# SCH_M5_Stick_DCC_Interface_2022-09-24.net
KiCad netlist of a schematic drawn in EasyEDA
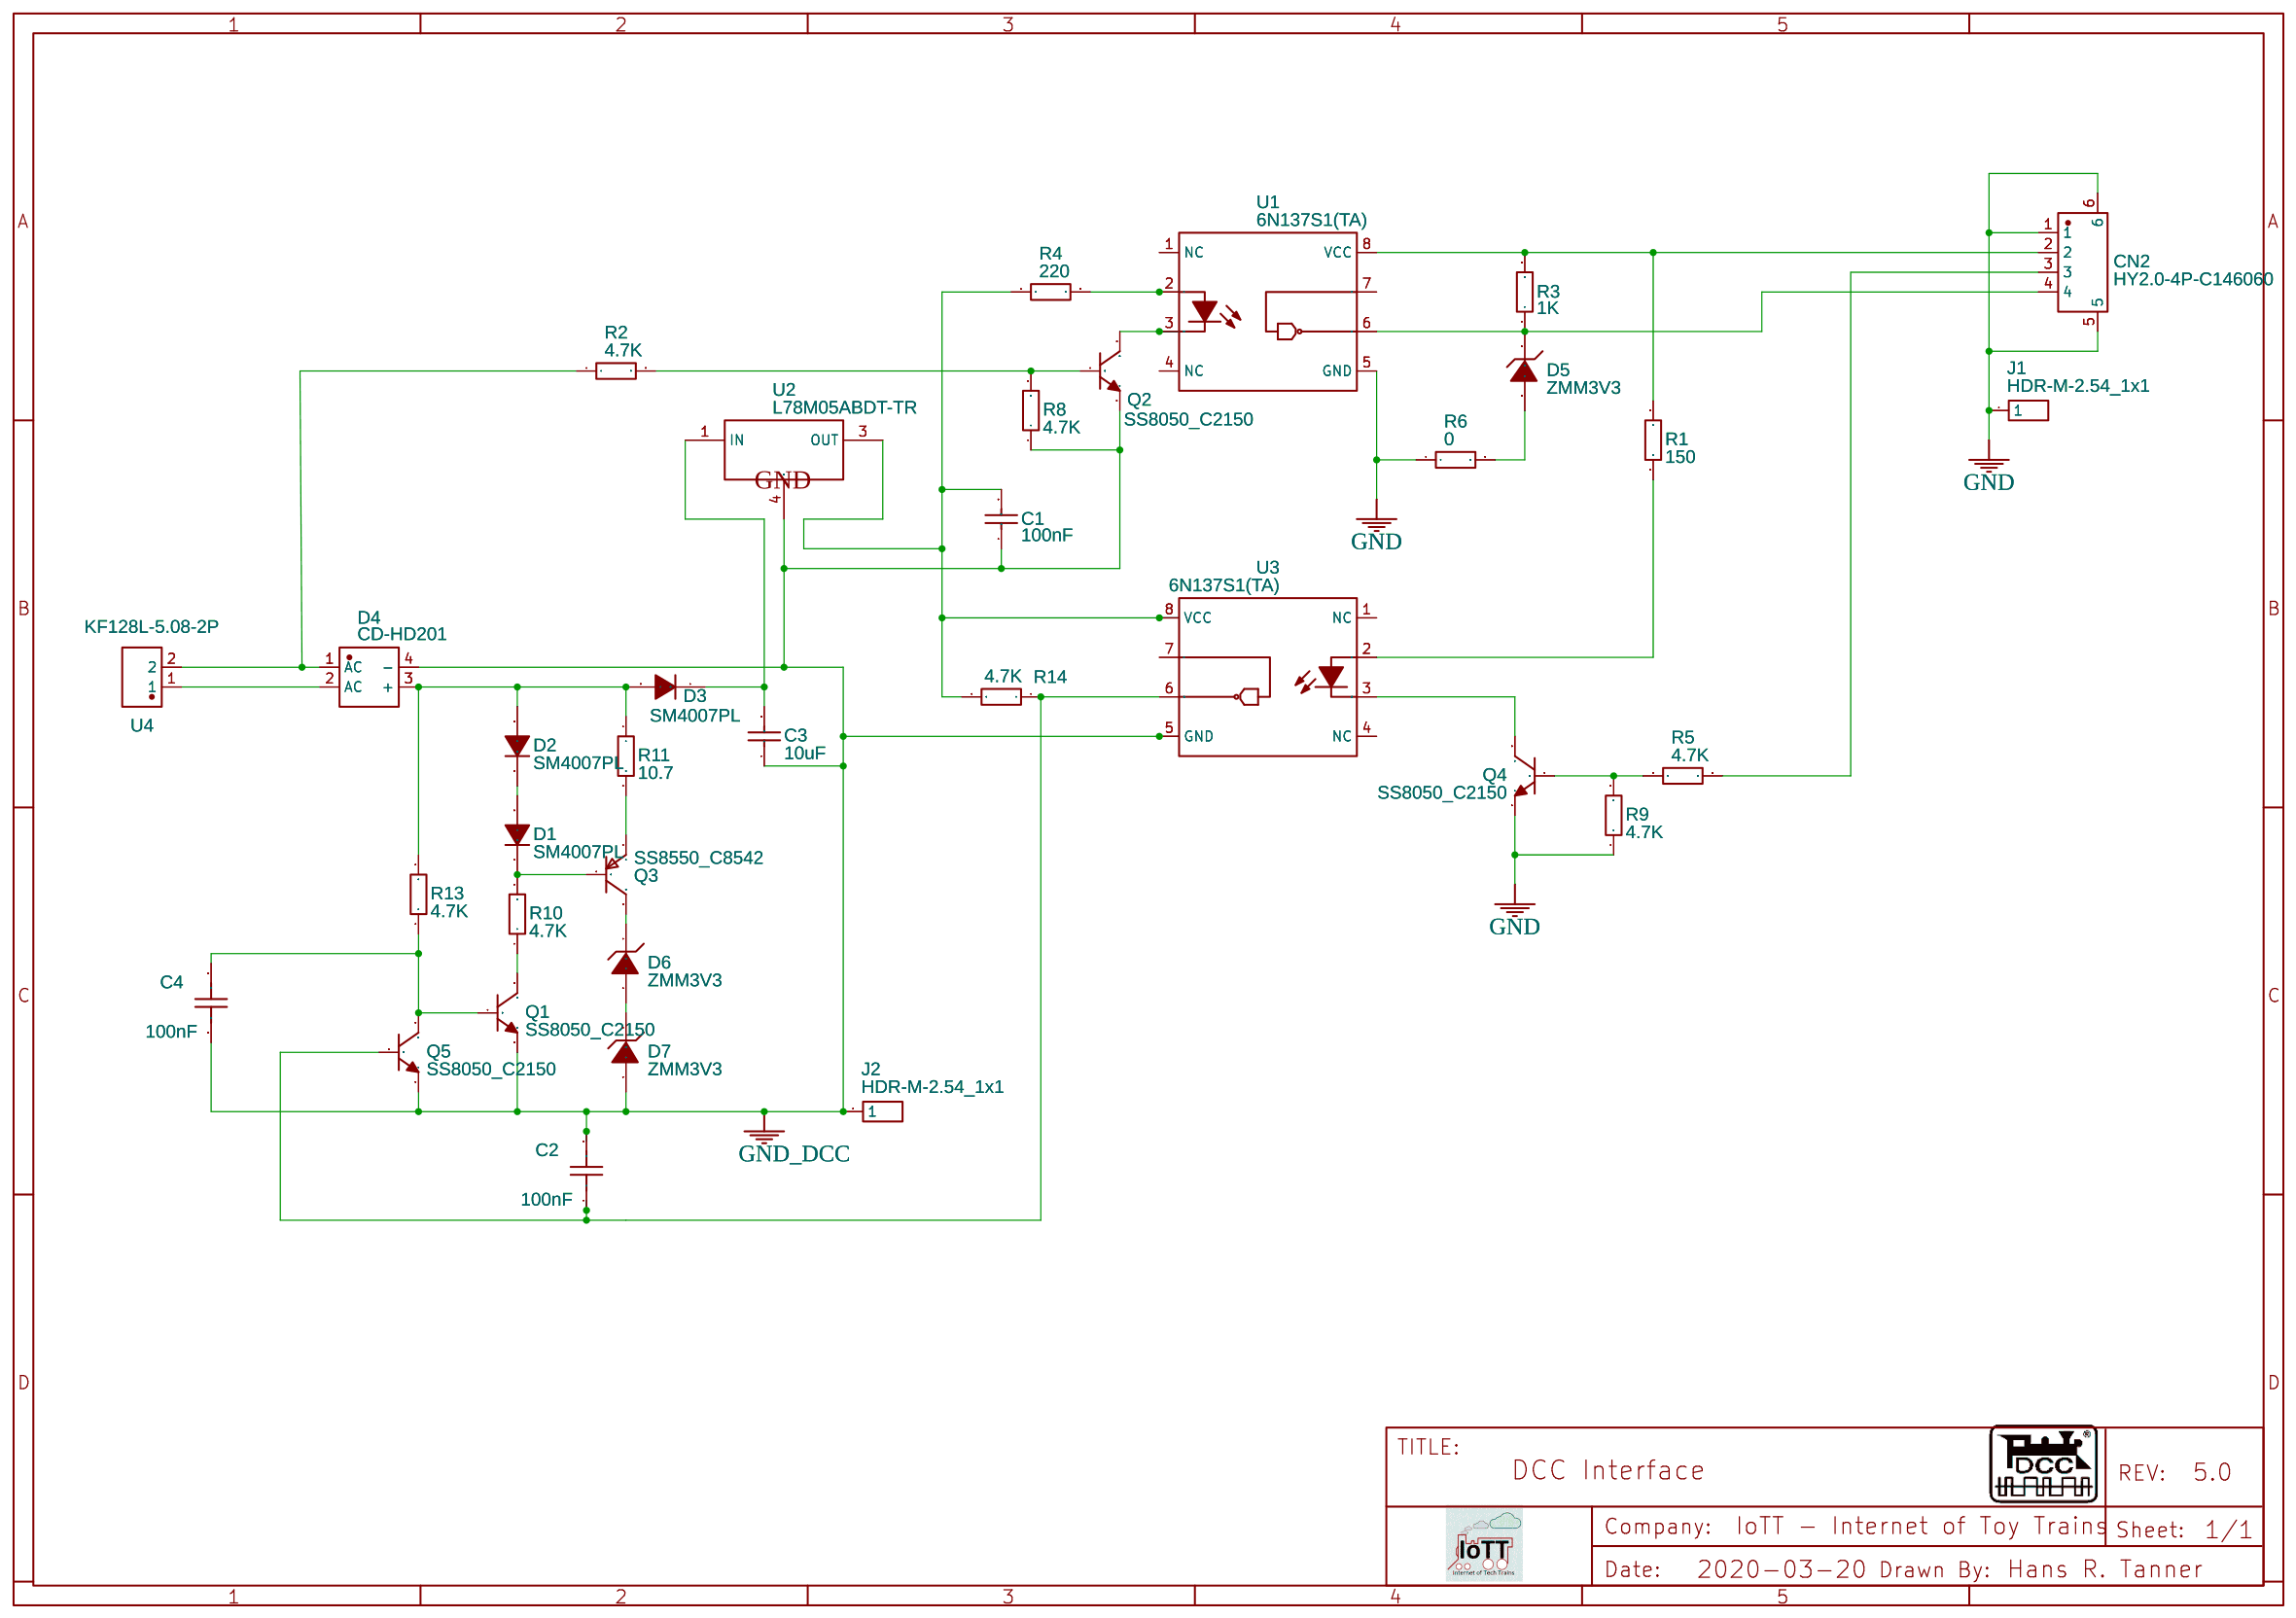
[diagram p0: schematic sheet]

(export (version "E")
  (design (tool "Eeschema 10.0.6"))
  (components
    (comp (ref "C1")
      (value "100nF")
      (fields
        (field (name "BOM_Manufacturer Part") "CL31B104KBCNNNC")
        (field (name "BOM_Supplier Part") "C24497")
      )
      (libsource (lib "") (part "CL31B104KBCNNNC"))
    )
    (comp (ref "C2")
      (value "100nF")
      (fields
        (field (name "BOM_Manufacturer Part") "CC0603KRX7R9BB104")
        (field (name "BOM_Supplier Part") "C14663")
      )
      (libsource (lib "") (part "CC0603KRX7R9BB104"))
    )
    (comp (ref "C3")
      (value "10uF")
      (fields
        (field (name "BOM_Manufacturer Part") "CL21A106KAYNNNE")
        (field (name "BOM_Supplier Part") "C15850")
      )
      (libsource (lib "") (part "CL21A106KAYNNNE"))
    )
    (comp (ref "C4")
      (value "100nF")
      (fields
        (field (name "BOM_Manufacturer Part") "CC0603KRX7R9BB104")
        (field (name "BOM_Supplier Part") "C14663")
      )
      (libsource (lib "") (part "CC0603KRX7R9BB104"))
    )
    (comp (ref "CN2")
      (value "HY2.0-4P-C146060")
      (fields (field (name "BOM_Supplier Part") "C146060"))
      (libsource (lib "") (part "HY2.0-4P-C146060"))
    )
    (comp (ref "D1")
      (value "SM4007PL")
      (fields (field (name "BOM_Supplier Part") "C64898"))
      (libsource (lib "") (part "SM4007PL_1"))
    )
    (comp (ref "D2")
      (value "SM4007PL")
      (fields (field (name "BOM_Supplier Part") "C64898"))
      (libsource (lib "") (part "SM4007PL_1"))
    )
    (comp (ref "D3")
      (value "SM4007PL")
      (fields (field (name "BOM_Supplier Part") "C64898"))
      (libsource (lib "") (part "SM4007PL"))
    )
    (comp (ref "D4")
      (value "CD-HD201")
      (fields (field (name "BOM_Supplier Part") "C143782"))
      (libsource (lib "") (part "CD-HD201"))
    )
    (comp (ref "D5")
      (value "ZMM3V3")
      (fields (field (name "BOM_Supplier Part") "C8056"))
      (libsource (lib "") (part "ZMM3V3"))
    )
    (comp (ref "D6")
      (value "ZMM3V3")
      (fields (field (name "BOM_Supplier Part") "C8056"))
      (libsource (lib "") (part "ZMM3V3"))
    )
    (comp (ref "D7")
      (value "ZMM3V3")
      (fields (field (name "BOM_Supplier Part") "C8056"))
      (libsource (lib "") (part "ZMM3V3"))
    )
    (comp (ref "J1")
      (value "HDR-M-2.54_1x1")
      (fields (field (name "BOM_Supplier Part") "C81276"))
      (libsource (lib "") (part "HDR-M-2.54_1x1"))
    )
    (comp (ref "J2")
      (value "HDR-M-2.54_1x1")
      (fields (field (name "BOM_Supplier Part") "C81276"))
      (libsource (lib "") (part "HDR-M-2.54_1x1"))
    )
    (comp (ref "Q1")
      (value "SS8050_C2150")
      (fields (field (name "BOM_Manufacturer Part") "SS8050") (field (name "BOM_Supplier Part") "C2150"))
      (libsource (lib "") (part "SS8050_C2150"))
    )
    (comp (ref "Q2")
      (value "SS8050_C2150")
      (fields (field (name "BOM_Manufacturer Part") "SS8050") (field (name "BOM_Supplier Part") "C2150"))
      (libsource (lib "") (part "SS8050_C2150"))
    )
    (comp (ref "Q3")
      (value "SS8550_C8542")
      (fields (field (name "BOM_Manufacturer Part") "SS8550") (field (name "BOM_Supplier Part") "C8542"))
      (libsource (lib "") (part "SS8550_C8542"))
    )
    (comp (ref "Q4")
      (value "SS8050_C2150")
      (fields (field (name "BOM_Manufacturer Part") "SS8050") (field (name "BOM_Supplier Part") "C2150"))
      (libsource (lib "") (part "SS8050_C2150_1"))
    )
    (comp (ref "Q5")
      (value "SS8050_C2150")
      (fields (field (name "BOM_Manufacturer Part") "SS8050") (field (name "BOM_Supplier Part") "C2150"))
      (libsource (lib "") (part "SS8050_C2150"))
    )
    (comp (ref "R1")
      (value "150")
      (fields
        (field (name "BOM_Manufacturer Part") "0603WAF1500T5E")
        (field (name "BOM_Supplier Part") "C22808")
      )
      (libsource (lib "") (part "0603WAF1500T5E_1"))
    )
    (comp (ref "R2")
      (value "4.7K")
      (fields
        (field (name "BOM_Manufacturer Part") "0603WAF4701T5E")
        (field (name "BOM_Supplier Part") "C23162")
      )
      (libsource (lib "") (part "0603WAF4701T5E_1"))
    )
    (comp (ref "R3")
      (value "1K")
      (fields
        (field (name "BOM_Manufacturer Part") "0402WGF1001TCE")
        (field (name "BOM_Supplier Part") "C11702")
      )
      (libsource (lib "") (part "0402WGF1001TCE"))
    )
    (comp (ref "R4")
      (value "220")
      (fields
        (field (name "BOM_Manufacturer Part") "0603WAF2200T5E")
        (field (name "BOM_Supplier Part") "C22962")
      )
      (libsource (lib "") (part "0603WAF1500T5E"))
    )
    (comp (ref "R5")
      (value "4.7K")
      (fields
        (field (name "BOM_Manufacturer Part") "0603WAF4701T5E")
        (field (name "BOM_Supplier Part") "C23162")
      )
      (libsource (lib "") (part "0603WAF4701T5E_1"))
    )
    (comp (ref "R6")
      (value "0")
      (fields
        (field (name "BOM_Manufacturer Part") "0402WGF0000TCE")
        (field (name "BOM_Supplier Part") "C17168")
      )
      (libsource (lib "") (part "0402WGF0000TCE"))
    )
    (comp (ref "R8")
      (value "4.7K")
      (fields
        (field (name "BOM_Manufacturer Part") "0603WAF4701T5E")
        (field (name "BOM_Supplier Part") "C23162")
      )
      (libsource (lib "") (part "0603WAF1001T5E"))
    )
    (comp (ref "R9")
      (value "4.7K")
      (fields
        (field (name "BOM_Manufacturer Part") "0603WAF4701T5E")
        (field (name "BOM_Supplier Part") "C23162")
      )
      (libsource (lib "") (part "0603WAF1001T5E"))
    )
    (comp (ref "R10")
      (value "4.7K")
      (fields
        (field (name "BOM_Manufacturer Part") "0603WAF4701T5E")
        (field (name "BOM_Supplier Part") "C23162")
      )
      (libsource (lib "") (part "0603WAF4701T5E"))
    )
    (comp (ref "R11")
      (value "10.7")
      (fields
        (field (name "BOM_Manufacturer Part") "0603WAF107JT5E")
        (field (name "BOM_Supplier Part") "C22774")
      )
      (libsource (lib "") (part "0603WAF107JT5E"))
    )
    (comp (ref "R13")
      (value "4.7K")
      (fields
        (field (name "BOM_Manufacturer Part") "0603WAF4701T5E")
        (field (name "BOM_Supplier Part") "C23162")
      )
      (libsource (lib "") (part "0603WAF4701T5E"))
    )
    (comp (ref "R14")
      (value "4.7K")
      (fields
        (field (name "BOM_Manufacturer Part") "0603WAF4701T5E")
        (field (name "BOM_Supplier Part") "C23162")
      )
      (libsource (lib "") (part "0603WAF1001T5E_1"))
    )
    (comp (ref "U1")
      (value "6N137S1(TA)")
      (fields (field (name "BOM_Supplier Part") "C110020"))
      (libsource (lib "") (part "6N137S1(TA)"))
    )
    (comp (ref "U2")
      (value "L78M05ABDT-TR")
      (fields (field (name "BOM_Supplier Part") "C58069"))
      (libsource (lib "") (part "L78M05ABDT-TR"))
    )
    (comp (ref "U3")
      (value "6N137S1(TA)")
      (fields (field (name "BOM_Supplier Part") "C110020"))
      (libsource (lib "") (part "6N137S1(TA)_1"))
    )
    (comp (ref "U4")
      (value "KF128L-5.08-2P")
      (fields (field (name "BOM_Supplier Part") "C474940"))
      (libsource (lib "") (part "KF128L-5.08-2P"))
    )
  )
  (nets
    (net (code "1") (name "GND") (class "Default")
      (node (ref "CN2") (pin "1") (pinfunction "1_1") (pintype "unspecified"))
      (node (ref "CN2") (pin "5") (pinfunction "5_5") (pintype "unspecified"))
      (node (ref "CN2") (pin "6") (pinfunction "6_6") (pintype "unspecified"))
      (node (ref "J1") (pin "1") (pinfunction "1_1") (pintype "input"))
      (node (ref "Q4") (pin "2") (pinfunction "E_2") (pintype "unspecified"))
      (node (ref "R6") (pin "1") (pinfunction "1_1") (pintype "input"))
      (node (ref "R9") (pin "1") (pinfunction "1_1") (pintype "input"))
      (node (ref "U1") (pin "5") (pinfunction "GND_5") (pintype "unspecified"))
    )
    (net (code "2") (name "GND_DCC") (class "Default")
      (node (ref "C1") (pin "1") (pinfunction "1_1") (pintype "input"))
      (node (ref "C2") (pin "2") (pinfunction "2_2") (pintype "unspecified"))
      (node (ref "C3") (pin "1") (pinfunction "1_1") (pintype "input"))
      (node (ref "C4") (pin "1") (pinfunction "1_1") (pintype "unspecified"))
      (node (ref "D4") (pin "4") (pinfunction "-_4") (pintype "unspecified"))
      (node (ref "D7") (pin "2") (pinfunction "A_2") (pintype "unspecified"))
      (node (ref "J2") (pin "1") (pinfunction "1_1") (pintype "input"))
      (node (ref "Q1") (pin "2") (pinfunction "E_2") (pintype "unspecified"))
      (node (ref "Q2") (pin "2") (pinfunction "E_2") (pintype "unspecified"))
      (node (ref "Q5") (pin "2") (pinfunction "E_2") (pintype "unspecified"))
      (node (ref "R8") (pin "1") (pinfunction "1_1") (pintype "input"))
      (node (ref "U2") (pin "4") (pinfunction "GND_4") (pintype "passive"))
      (node (ref "U3") (pin "5") (pinfunction "GND_5") (pintype "unspecified"))
    )
    (net (code "3") (name "Net-(CN2-Pad3)") (class "Default")
      (node (ref "CN2") (pin "3") (pinfunction "3_3") (pintype "unspecified"))
      (node (ref "R5") (pin "2") (pinfunction "2_2") (pintype "input"))
    )
    (net (code "4") (name "Net-(D1-A)") (class "Default")
      (node (ref "D1") (pin "2") (pinfunction "A_2") (pintype "unspecified"))
      (node (ref "D2") (pin "1") (pinfunction "C_1") (pintype "unspecified"))
    )
    (net (code "5") (name "Net-(D1-C)") (class "Default")
      (node (ref "D1") (pin "1") (pinfunction "C_1") (pintype "unspecified"))
      (node (ref "Q3") (pin "1") (pinfunction "B_1") (pintype "unspecified"))
      (node (ref "R10") (pin "2") (pinfunction "2_2") (pintype "input"))
    )
    (net (code "6") (name "Net-(D2-A)") (class "Default")
      (node (ref "D2") (pin "2") (pinfunction "A_2") (pintype "unspecified"))
      (node (ref "D3") (pin "2") (pinfunction "A_2") (pintype "unspecified"))
      (node (ref "D4") (pin "3") (pinfunction "+_3") (pintype "unspecified"))
      (node (ref "R11") (pin "1") (pinfunction "1_1") (pintype "input"))
      (node (ref "R13") (pin "2") (pinfunction "2_2") (pintype "input"))
    )
    (net (code "7") (name "Net-(D3-C)") (class "Default")
      (node (ref "C3") (pin "2") (pinfunction "2_2") (pintype "input"))
      (node (ref "D3") (pin "1") (pinfunction "C_1") (pintype "unspecified"))
      (node (ref "U2") (pin "1") (pinfunction "IN_1") (pintype "passive"))
    )
    (net (code "8") (name "Net-(D4-AC-Pad1)") (class "Default")
      (node (ref "D4") (pin "1") (pinfunction "AC_1") (pintype "unspecified"))
      (node (ref "R2") (pin "1") (pinfunction "1_1") (pintype "input"))
      (node (ref "U4") (pin "2") (pinfunction "2_2") (pintype "unspecified"))
    )
    (net (code "9") (name "Net-(D4-AC-Pad2)") (class "Default")
      (node (ref "D4") (pin "2") (pinfunction "AC_2") (pintype "unspecified"))
      (node (ref "U4") (pin "1") (pinfunction "1_1") (pintype "unspecified"))
    )
    (net (code "10") (name "Net-(D5-A)") (class "Default")
      (node (ref "D5") (pin "2") (pinfunction "A_2") (pintype "unspecified"))
      (node (ref "R6") (pin "2") (pinfunction "2_2") (pintype "input"))
    )
    (net (code "11") (name "Net-(D5-C)") (class "Default")
      (node (ref "CN2") (pin "4") (pinfunction "4_4") (pintype "unspecified"))
      (node (ref "D5") (pin "1") (pinfunction "C_1") (pintype "unspecified"))
      (node (ref "R3") (pin "1") (pinfunction "1_1") (pintype "input"))
      (node (ref "U1") (pin "6") (pinfunction "VOUT_6") (pintype "unspecified"))
    )
    (net (code "12") (name "Net-(D6-A)") (class "Default")
      (node (ref "D6") (pin "2") (pinfunction "A_2") (pintype "unspecified"))
      (node (ref "D7") (pin "1") (pinfunction "C_1") (pintype "unspecified"))
    )
    (net (code "13") (name "Net-(D6-C)") (class "Default")
      (node (ref "D6") (pin "1") (pinfunction "C_1") (pintype "unspecified"))
      (node (ref "Q3") (pin "3") (pinfunction "C_3") (pintype "unspecified"))
    )
    (net (code "14") (name "Net-(Q1-B)") (class "Default")
      (node (ref "C4") (pin "2") (pinfunction "2_2") (pintype "unspecified"))
      (node (ref "Q1") (pin "1") (pinfunction "B_1") (pintype "unspecified"))
      (node (ref "Q5") (pin "3") (pinfunction "C_3") (pintype "unspecified"))
      (node (ref "R13") (pin "1") (pinfunction "1_1") (pintype "input"))
    )
    (net (code "15") (name "Net-(Q1-C)") (class "Default")
      (node (ref "Q1") (pin "3") (pinfunction "C_3") (pintype "unspecified"))
      (node (ref "R10") (pin "1") (pinfunction "1_1") (pintype "input"))
    )
    (net (code "16") (name "Net-(Q2-B)") (class "Default")
      (node (ref "Q2") (pin "1") (pinfunction "B_1") (pintype "unspecified"))
      (node (ref "R2") (pin "2") (pinfunction "2_2") (pintype "input"))
      (node (ref "R8") (pin "2") (pinfunction "2_2") (pintype "input"))
    )
    (net (code "17") (name "Net-(Q2-C)") (class "Default")
      (node (ref "Q2") (pin "3") (pinfunction "C_3") (pintype "unspecified"))
      (node (ref "U1") (pin "3") (pinfunction "CAT_3") (pintype "unspecified"))
    )
    (net (code "18") (name "Net-(Q3-E)") (class "Default")
      (node (ref "Q3") (pin "2") (pinfunction "E_2") (pintype "unspecified"))
      (node (ref "R11") (pin "2") (pinfunction "2_2") (pintype "input"))
    )
    (net (code "19") (name "Net-(Q4-B)") (class "Default")
      (node (ref "Q4") (pin "1") (pinfunction "B_1") (pintype "unspecified"))
      (node (ref "R5") (pin "1") (pinfunction "1_1") (pintype "input"))
      (node (ref "R9") (pin "2") (pinfunction "2_2") (pintype "input"))
    )
    (net (code "20") (name "Net-(Q4-C)") (class "Default")
      (node (ref "Q4") (pin "3") (pinfunction "C_3") (pintype "unspecified"))
      (node (ref "U3") (pin "3") (pinfunction "CAT_3") (pintype "unspecified"))
    )
    (net (code "21") (name "Net-(Q5-B)") (class "Default")
      (node (ref "C2") (pin "1") (pinfunction "1_1") (pintype "unspecified"))
      (node (ref "Q5") (pin "1") (pinfunction "B_1") (pintype "unspecified"))
      (node (ref "R14") (pin "1") (pinfunction "1_1") (pintype "input"))
      (node (ref "U3") (pin "6") (pinfunction "VOUT_6") (pintype "unspecified"))
    )
    (net (code "22") (name "Net-(U1-AN)") (class "Default")
      (node (ref "R4") (pin "2") (pinfunction "2_2") (pintype "input"))
      (node (ref "U1") (pin "2") (pinfunction "AN_2") (pintype "unspecified"))
    )
    (net (code "23") (name "Net-(U1-VCC)") (class "Default")
      (node (ref "CN2") (pin "2") (pinfunction "2_2") (pintype "unspecified"))
      (node (ref "R1") (pin "2") (pinfunction "2_2") (pintype "input"))
      (node (ref "R3") (pin "2") (pinfunction "2_2") (pintype "input"))
      (node (ref "U1") (pin "8") (pinfunction "VCC_8") (pintype "unspecified"))
    )
    (net (code "24") (name "Net-(U2-OUT)") (class "Default")
      (node (ref "C1") (pin "2") (pinfunction "2_2") (pintype "input"))
      (node (ref "R14") (pin "2") (pinfunction "2_2") (pintype "input"))
      (node (ref "R4") (pin "1") (pinfunction "1_1") (pintype "input"))
      (node (ref "U2") (pin "3") (pinfunction "OUT_3") (pintype "passive"))
      (node (ref "U3") (pin "8") (pinfunction "VCC_8") (pintype "unspecified"))
    )
    (net (code "25") (name "Net-(U3-AN)") (class "Default")
      (node (ref "R1") (pin "1") (pinfunction "1_1") (pintype "input"))
      (node (ref "U3") (pin "2") (pinfunction "AN_2") (pintype "unspecified"))
    )
    (net (code "26") (name "unconnected-(U1-NC-Pad1)") (class "Default")
      (node (ref "U1") (pin "1") (pinfunction "NC_1") (pintype "unspecified"))
    )
    (net (code "27") (name "unconnected-(U1-NC-Pad4)") (class "Default")
      (node (ref "U1") (pin "4") (pinfunction "NC_4") (pintype "unspecified"))
    )
    (net (code "28") (name "unconnected-(U1-VE-Pad7)") (class "Default")
      (node (ref "U1") (pin "7") (pinfunction "VE_7") (pintype "unspecified"))
    )
    (net (code "29") (name "unconnected-(U3-NC-Pad1)") (class "Default")
      (node (ref "U3") (pin "1") (pinfunction "NC_1") (pintype "unspecified"))
    )
    (net (code "30") (name "unconnected-(U3-NC-Pad4)") (class "Default")
      (node (ref "U3") (pin "4") (pinfunction "NC_4") (pintype "unspecified"))
    )
    (net (code "31") (name "unconnected-(U3-VE-Pad7)") (class "Default")
      (node (ref "U3") (pin "7") (pinfunction "VE_7") (pintype "unspecified"))
    )
  )
)
